# REO_ECG.net
KiCad netlist of a schematic drawn in Altium Designer
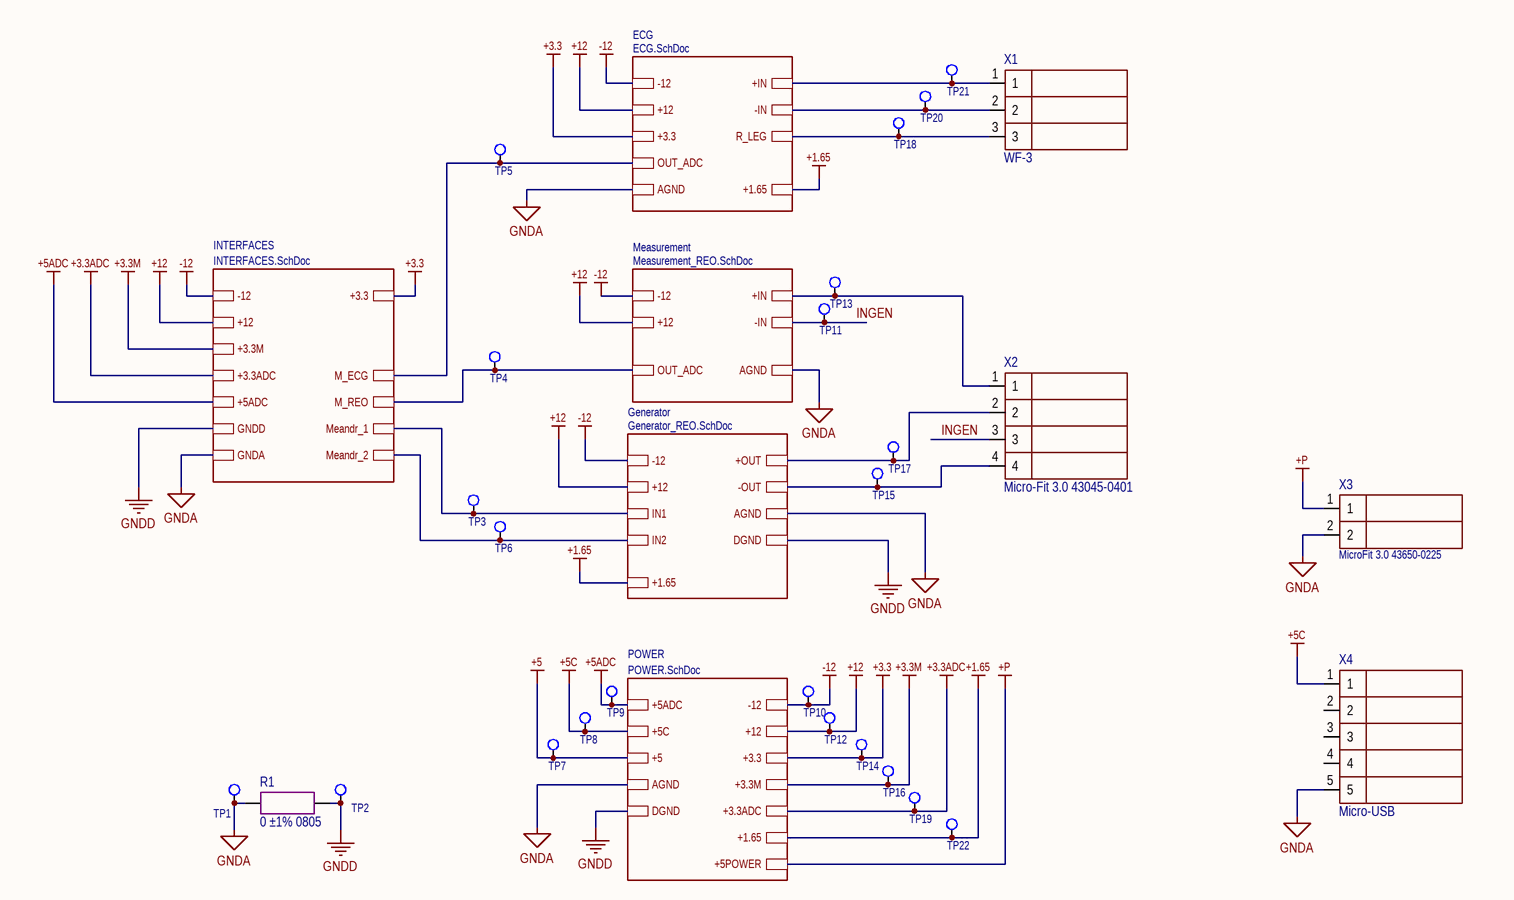
[diagram p0: REO_ECG.SchDoc]

(export (version "E")
  (design (tool "Eeschema 10.0.6"))
  (components
    (comp (ref "R1")
      (value "0 ±1% 0805")
      (footprint "RES: SMD 0805 MD IPC 782")
      (libsource (lib "UOMP_resistors") (part "0 ±1% 0805"))
    )
    (comp (ref "TP1")
      (value "Test point")
      (footprint "Test Point")
      (libsource (lib "UOMP_primitives") (part "Test point"))
    )
    (comp (ref "TP2")
      (value "Test point")
      (footprint "Test Point")
      (libsource (lib "UOMP_primitives") (part "Test point"))
    )
    (comp (ref "TP3")
      (value "Test point")
      (footprint "Test Point")
      (libsource (lib "UOMP_primitives") (part "Test point"))
    )
    (comp (ref "TP4")
      (value "Test point")
      (footprint "Test Point")
      (libsource (lib "UOMP_primitives") (part "Test point"))
    )
    (comp (ref "TP5")
      (value "Test point")
      (footprint "Test Point")
      (libsource (lib "UOMP_primitives") (part "Test point"))
    )
    (comp (ref "TP6")
      (value "Test point")
      (footprint "Test Point")
      (libsource (lib "UOMP_primitives") (part "Test point"))
    )
    (comp (ref "TP7")
      (value "Test point")
      (footprint "Test Point")
      (libsource (lib "UOMP_primitives") (part "Test point"))
    )
    (comp (ref "TP8")
      (value "Test point")
      (footprint "Test Point")
      (libsource (lib "UOMP_primitives") (part "Test point"))
    )
    (comp (ref "TP9")
      (value "Test point")
      (footprint "Test Point")
      (libsource (lib "UOMP_primitives") (part "Test point"))
    )
    (comp (ref "TP10")
      (value "Test point")
      (footprint "Test Point")
      (libsource (lib "UOMP_primitives") (part "Test point"))
    )
    (comp (ref "TP11")
      (value "Test point")
      (footprint "Test Point")
      (libsource (lib "UOMP_primitives") (part "Test point"))
    )
    (comp (ref "TP12")
      (value "Test point")
      (footprint "Test Point")
      (libsource (lib "UOMP_primitives") (part "Test point"))
    )
    (comp (ref "TP13")
      (value "Test point")
      (footprint "Test Point")
      (libsource (lib "UOMP_primitives") (part "Test point"))
    )
    (comp (ref "TP14")
      (value "Test point")
      (footprint "Test Point")
      (libsource (lib "UOMP_primitives") (part "Test point"))
    )
    (comp (ref "TP15")
      (value "Test point")
      (footprint "Test Point")
      (libsource (lib "UOMP_primitives") (part "Test point"))
    )
    (comp (ref "TP16")
      (value "Test point")
      (footprint "Test Point")
      (libsource (lib "UOMP_primitives") (part "Test point"))
    )
    (comp (ref "TP17")
      (value "Test point")
      (footprint "Test Point")
      (libsource (lib "UOMP_primitives") (part "Test point"))
    )
    (comp (ref "TP18")
      (value "Test point")
      (footprint "Test Point")
      (libsource (lib "UOMP_primitives") (part "Test point"))
    )
    (comp (ref "TP19")
      (value "Test point")
      (footprint "Test Point")
      (libsource (lib "UOMP_primitives") (part "Test point"))
    )
    (comp (ref "TP20")
      (value "Test point")
      (footprint "Test Point")
      (libsource (lib "UOMP_primitives") (part "Test point"))
    )
    (comp (ref "TP21")
      (value "Test point")
      (footprint "Test Point")
      (libsource (lib "UOMP_primitives") (part "Test point"))
    )
    (comp (ref "TP22")
      (value "Test point")
      (footprint "Test Point")
      (libsource (lib "UOMP_primitives") (part "Test point"))
    )
    (comp (ref "X1")
      (value "WF-3")
      (footprint "CON: 3pin wf-3")
      (libsource (lib "UOMP connectors") (part "3 pin WF-3"))
    )
    (comp (ref "X2")
      (value "Micro-Fit 3.0 43045-0401")
      (footprint "CON: 4pin Molex MicroFit 3.0 43045-0401")
      (libsource (lib "UOMP_connectors") (part "4 pin MicroFit DR R Molex"))
    )
    (comp (ref "X3")
      (value "MicroFit 3.0 43650-0225")
      (footprint "CON: 2pin Molex MicroFit 3.0 43650-0225")
      (libsource (lib "UOMP_connectors") (part "2 pin MicroFit SR Molex"))
    )
    (comp (ref "X4")
      (value "Micro-USB")
      (footprint "CON: 5pin USB Micro")
      (libsource (lib "UOMP_connectors") (part "5 pin USB Micro SMD"))
    )
  )
  (nets
    (net (code "1") (name "+1.65") (class "Default")
      (node (ref "TP22") (pin "1") (pinfunction "1_1") (pintype "passive"))
    )
    (net (code "2") (name "+3.3") (class "Default")
      (node (ref "TP14") (pin "1") (pinfunction "1_1") (pintype "passive"))
    )
    (net (code "3") (name "+3.3ADC") (class "Default")
      (node (ref "TP19") (pin "1") (pinfunction "1_1") (pintype "passive"))
    )
    (net (code "4") (name "+3.3M") (class "Default")
      (node (ref "TP16") (pin "1") (pinfunction "1_1") (pintype "passive"))
    )
    (net (code "5") (name "+5") (class "Default")
      (node (ref "TP7") (pin "1") (pinfunction "1_1") (pintype "passive"))
    )
    (net (code "6") (name "+5ADC") (class "Default")
      (node (ref "TP9") (pin "1") (pinfunction "1_1") (pintype "passive"))
    )
    (net (code "7") (name "+5C") (class "Default")
      (node (ref "TP8") (pin "1") (pinfunction "1_1") (pintype "passive"))
      (node (ref "X4") (pin "1") (pinfunction "1_1") (pintype "passive"))
    )
    (net (code "8") (name "+12") (class "Default")
      (node (ref "TP12") (pin "1") (pinfunction "1_1") (pintype "passive"))
    )
    (net (code "9") (name "+P") (class "Default")
      (node (ref "X3") (pin "1") (pinfunction "1_1") (pintype "passive"))
    )
    (net (code "10") (name "-12") (class "Default")
      (node (ref "TP10") (pin "1") (pinfunction "1_1") (pintype "passive"))
    )
    (net (code "12") (name "/+IN_1") (class "Default")
      (node (ref "TP21") (pin "1") (pinfunction "1_1") (pintype "passive"))
      (node (ref "X1") (pin "1") (pinfunction "1_1") (pintype "passive"))
    )
    (net (code "15") (name "/-IN_1") (class "Default")
      (node (ref "TP20") (pin "1") (pinfunction "1_1") (pintype "passive"))
      (node (ref "X1") (pin "2") (pinfunction "2_2") (pintype "passive"))
    )
    (net (code "20") (name "/IN1") (class "Default")
      (node (ref "TP3") (pin "1") (pinfunction "1_1") (pintype "passive"))
    )
    (net (code "21") (name "/IN2") (class "Default")
      (node (ref "TP6") (pin "1") (pinfunction "1_1") (pintype "passive"))
    )
    (net (code "22") (name "/INGEN") (class "Default")
      (node (ref "TP11") (pin "1") (pinfunction "1_1") (pintype "passive"))
      (node (ref "X2") (pin "3") (pinfunction "3_3") (pintype "passive"))
    )
    (net (code "23") (name "/M_ECG") (class "Default")
      (node (ref "TP5") (pin "1") (pinfunction "1_1") (pintype "passive"))
    )
    (net (code "24") (name "/M_REO") (class "Default")
      (node (ref "TP4") (pin "1") (pinfunction "1_1") (pintype "passive"))
    )
    (net (code "25") (name "/R_LEG") (class "Default")
      (node (ref "TP18") (pin "1") (pinfunction "1_1") (pintype "passive"))
      (node (ref "X1") (pin "3") (pinfunction "3_3") (pintype "passive"))
    )
    (net (code "26") (name "GNDA") (class "Default")
      (node (ref "R1") (pin "1") (pinfunction "1_1") (pintype "passive"))
      (node (ref "TP1") (pin "1") (pinfunction "1_1") (pintype "passive"))
      (node (ref "X3") (pin "2") (pinfunction "2_2") (pintype "passive"))
      (node (ref "X4") (pin "5") (pinfunction "5_5") (pintype "passive"))
    )
    (net (code "27") (name "GNDD") (class "Default")
      (node (ref "R1") (pin "2") (pinfunction "2_2") (pintype "passive"))
      (node (ref "TP2") (pin "1") (pinfunction "1_1") (pintype "passive"))
    )
    (net (code "28") (name "Net-(TP13-Pad1)") (class "Default")
      (node (ref "TP13") (pin "1") (pinfunction "1_1") (pintype "passive"))
      (node (ref "X2") (pin "1") (pinfunction "1_1") (pintype "passive"))
    )
    (net (code "29") (name "Net-(TP15-Pad1)") (class "Default")
      (node (ref "TP15") (pin "1") (pinfunction "1_1") (pintype "passive"))
      (node (ref "X2") (pin "4") (pinfunction "4_4") (pintype "passive"))
    )
    (net (code "30") (name "Net-(TP17-Pad1)") (class "Default")
      (node (ref "TP17") (pin "1") (pinfunction "1_1") (pintype "passive"))
      (node (ref "X2") (pin "2") (pinfunction "2_2") (pintype "passive"))
    )
    (net (code "31") (name "unconnected-(X4-Pad2)") (class "Default")
      (node (ref "X4") (pin "2") (pinfunction "2_2") (pintype "passive"))
    )
    (net (code "32") (name "unconnected-(X4-Pad3)") (class "Default")
      (node (ref "X4") (pin "3") (pinfunction "3_3") (pintype "passive"))
    )
    (net (code "33") (name "unconnected-(X4-Pad4)") (class "Default")
      (node (ref "X4") (pin "4") (pinfunction "4_4") (pintype "passive"))
    )
  )
)
